# yedek_aviyonik.net
KiCad netlist of a schematic drawn in Altium Designer
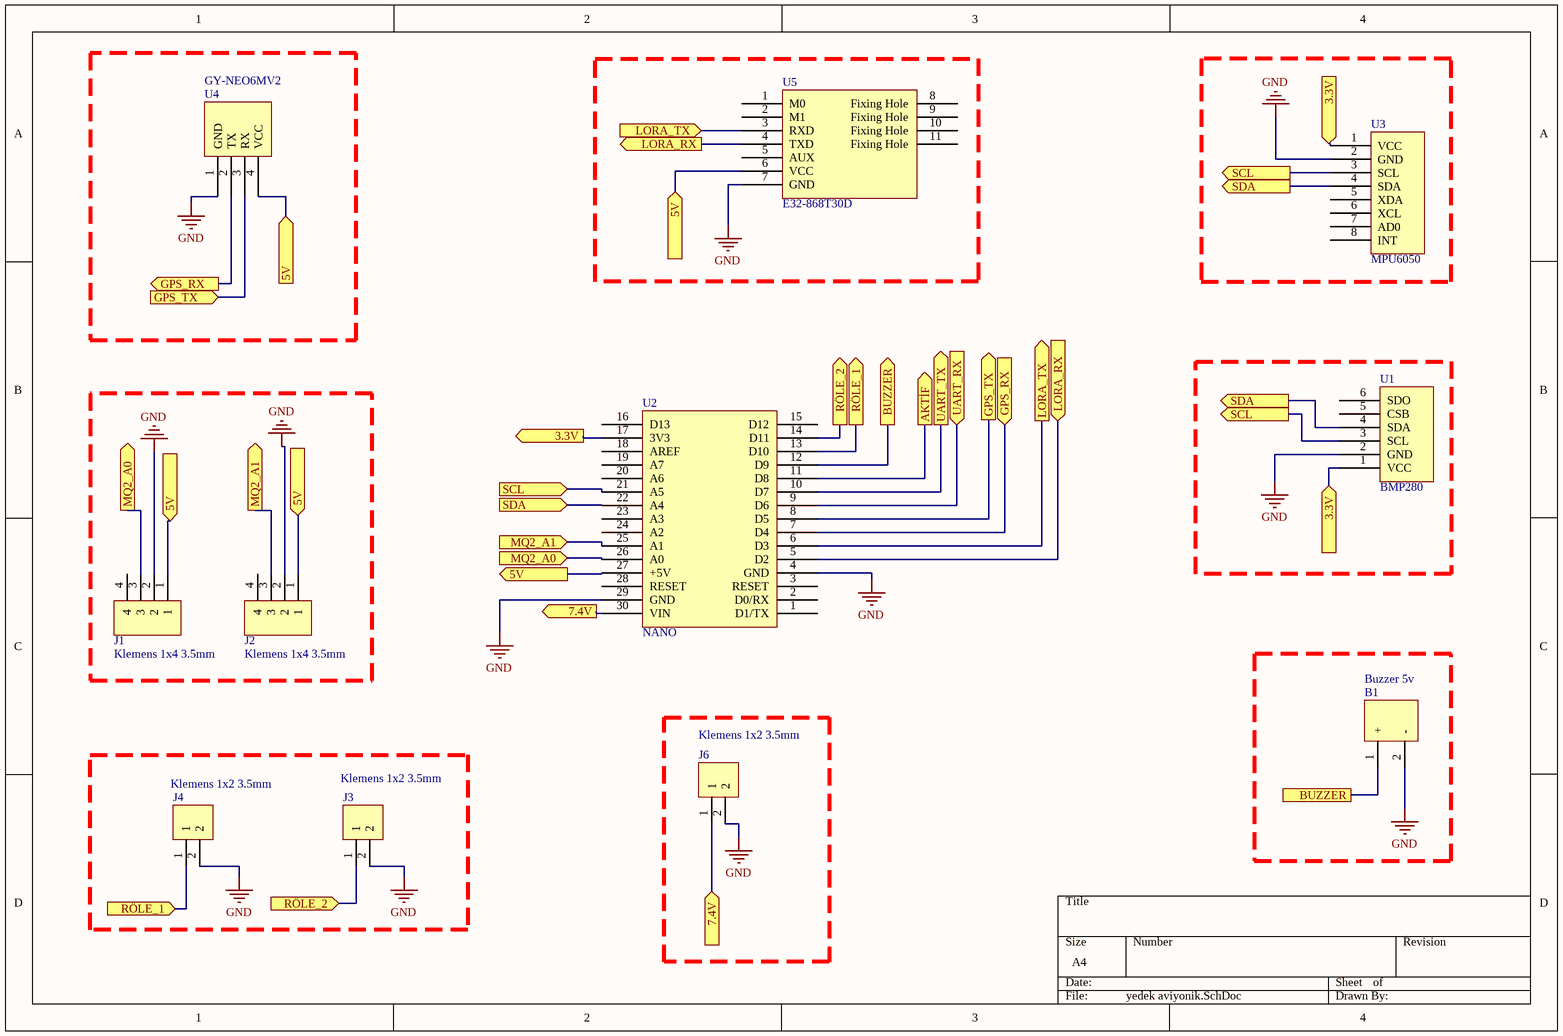
[diagram p0: yedek aviyonik.SchDoc]

(export (version "E")
  (design (tool "Eeschema 10.0.6"))
  (components
    (comp (ref "B1")
      (value "Buzzer 5v")
      (footprint "Buzzer 5v")
      (libsource (lib "deneme") (part "Buzzer 5v"))
    )
    (comp (ref "J1")
      (value "Klemens 1x4 3.5mm")
      (footprint "Klemens 1x4 - 3.5mm")
      (description "Klemens 1x2 3.5mm")
      (libsource (lib "deneme") (part "Klemens 1x4 3.5mm"))
    )
    (comp (ref "J2")
      (value "Klemens 1x4 3.5mm")
      (footprint "Klemens 1x4 - 3.5mm")
      (description "Klemens 1x2 3.5mm")
      (libsource (lib "deneme") (part "Klemens 1x4 3.5mm"))
    )
    (comp (ref "J3")
      (value "Klemens 1x2 3.5mm")
      (footprint "Klemens 1x2 - 3.5mm")
      (libsource (lib "deneme") (part "Klemens 1x2 3.5mm"))
    )
    (comp (ref "J4")
      (value "Klemens 1x2 3.5mm")
      (footprint "Klemens 1x2 - 3.5mm")
      (libsource (lib "deneme") (part "Klemens 1x2 3.5mm"))
    )
    (comp (ref "J6")
      (value "Klemens 1x2 3.5mm")
      (footprint "Klemens 1x2 - 3.5mm")
      (libsource (lib "deneme_yedek") (part "Klemens 1x2 3.5mm"))
    )
    (comp (ref "U1") (value "BMP280") (footprint "BMP280") (libsource (lib "deneme") (part "BMP280")))
    (comp (ref "U2") (value "NANO") (footprint "nano") (libsource (lib "deneme") (part "NANO")))
    (comp (ref "U3") (value "MPU6050") (footprint "MPU6050") (libsource (lib "deneme") (part "MPU6050")))
    (comp (ref "U4")
      (value "GY-NEO6MV2")
      (footprint "GY-NEO6MV2")
      (libsource (lib "deneme") (part "GY-NEO6MV2"))
    )
    (comp (ref "U5")
      (value "E32-868T30D")
      (footprint "E32-868T30D")
      (libsource (lib "deneme") (part "E32-868T30D"))
    )
  )
  (nets
    (net (code "1") (name "/3.3V") (class "Default")
      (node (ref "U1") (pin "1") (pinfunction "VCC_1") (pintype "passive"))
      (node (ref "U2") (pin "17") (pinfunction "3V3_17") (pintype "passive"))
      (node (ref "U3") (pin "1") (pinfunction "VCC_1") (pintype "passive"))
    )
    (net (code "2") (name "/5V") (class "Default")
      (node (ref "J1") (pin "1") (pinfunction "1_1") (pintype "passive"))
      (node (ref "J2") (pin "1") (pinfunction "1_1") (pintype "passive"))
      (node (ref "U2") (pin "27") (pinfunction "+5V_27") (pintype "passive"))
      (node (ref "U4") (pin "4") (pinfunction "VCC_4") (pintype "passive"))
      (node (ref "U5") (pin "6") (pinfunction "VCC_6") (pintype "passive"))
    )
    (net (code "3") (name "/7.4V") (class "Default")
      (node (ref "J6") (pin "1") (pinfunction "1_1") (pintype "passive"))
      (node (ref "U2") (pin "30") (pinfunction "VIN_30") (pintype "passive"))
    )
    (net (code "4") (name "/AKTİF") (class "Default")
      (node (ref "U2") (pin "11") (pinfunction "D8_11") (pintype "passive"))
    )
    (net (code "5") (name "/BUZZER") (class "Default")
      (node (ref "B1") (pin "1") (pinfunction "+_1") (pintype "passive"))
      (node (ref "U2") (pin "12") (pinfunction "D9_12") (pintype "passive"))
    )
    (net (code "6") (name "/GPS_RX") (class "Default")
      (node (ref "U2") (pin "7") (pinfunction "D4_7") (pintype "passive"))
      (node (ref "U4") (pin "2") (pinfunction "TX_2") (pintype "passive"))
    )
    (net (code "7") (name "/GPS_TX") (class "Default")
      (node (ref "U2") (pin "8") (pinfunction "D5_8") (pintype "passive"))
      (node (ref "U4") (pin "3") (pinfunction "RX_3") (pintype "passive"))
    )
    (net (code "8") (name "/LORA_RX") (class "Default")
      (node (ref "U2") (pin "5") (pinfunction "D2_5") (pintype "passive"))
      (node (ref "U5") (pin "4") (pinfunction "TXD_4") (pintype "passive"))
    )
    (net (code "9") (name "/LORA_TX") (class "Default")
      (node (ref "U2") (pin "6") (pinfunction "D3_6") (pintype "passive"))
      (node (ref "U5") (pin "3") (pinfunction "RXD_3") (pintype "passive"))
    )
    (net (code "10") (name "/MQ2_A0") (class "Default")
      (node (ref "J1") (pin "3") (pinfunction "3_3") (pintype "passive"))
      (node (ref "U2") (pin "26") (pinfunction "A0_26") (pintype "passive"))
    )
    (net (code "11") (name "/MQ2_A1") (class "Default")
      (node (ref "J2") (pin "3") (pinfunction "3_3") (pintype "passive"))
      (node (ref "U2") (pin "25") (pinfunction "A1_25") (pintype "passive"))
    )
    (net (code "12") (name "/RÖLE_1") (class "Default")
      (node (ref "J4") (pin "1") (pinfunction "1_1") (pintype "passive"))
      (node (ref "U2") (pin "13") (pinfunction "D10_13") (pintype "passive"))
    )
    (net (code "13") (name "/RÖLE_2") (class "Default")
      (node (ref "J3") (pin "1") (pinfunction "1_1") (pintype "passive"))
      (node (ref "U2") (pin "14") (pinfunction "D11_14") (pintype "passive"))
    )
    (net (code "14") (name "/SCL") (class "Default")
      (node (ref "U1") (pin "3") (pinfunction "SCL_3") (pintype "passive"))
      (node (ref "U2") (pin "21") (pinfunction "A5_21") (pintype "passive"))
      (node (ref "U3") (pin "3") (pinfunction "SCL_3") (pintype "passive"))
    )
    (net (code "15") (name "/SDA") (class "Default")
      (node (ref "U1") (pin "4") (pinfunction "SDA_4") (pintype "passive"))
      (node (ref "U2") (pin "22") (pinfunction "A4_22") (pintype "passive"))
      (node (ref "U3") (pin "4") (pinfunction "SDA_4") (pintype "passive"))
    )
    (net (code "16") (name "/UART_RX") (class "Default")
      (node (ref "U2") (pin "9") (pinfunction "D6_9") (pintype "passive"))
    )
    (net (code "17") (name "/UART_TX") (class "Default")
      (node (ref "U2") (pin "10") (pinfunction "D7_10") (pintype "passive"))
    )
    (net (code "18") (name "GND") (class "Default")
      (node (ref "B1") (pin "2") (pinfunction "-_2") (pintype "passive"))
      (node (ref "J1") (pin "2") (pinfunction "2_2") (pintype "passive"))
      (node (ref "J2") (pin "2") (pinfunction "2_2") (pintype "passive"))
      (node (ref "J3") (pin "2") (pinfunction "2_2") (pintype "passive"))
      (node (ref "J4") (pin "2") (pinfunction "2_2") (pintype "passive"))
      (node (ref "J6") (pin "2") (pinfunction "2_2") (pintype "passive"))
      (node (ref "U1") (pin "2") (pinfunction "GND_2") (pintype "passive"))
      (node (ref "U2") (pin "29") (pinfunction "GND_29") (pintype "passive"))
      (node (ref "U2") (pin "4") (pinfunction "GND_4") (pintype "passive"))
      (node (ref "U3") (pin "2") (pinfunction "GND_2") (pintype "passive"))
      (node (ref "U4") (pin "1") (pinfunction "GND_1") (pintype "passive"))
      (node (ref "U5") (pin "7") (pinfunction "GND_7") (pintype "passive"))
    )
    (net (code "19") (name "unconnected-(J1-Pad4)") (class "Default")
      (node (ref "J1") (pin "4") (pinfunction "4_4") (pintype "passive"))
    )
    (net (code "20") (name "unconnected-(J2-Pad4)") (class "Default")
      (node (ref "J2") (pin "4") (pinfunction "4_4") (pintype "passive"))
    )
    (net (code "21") (name "unconnected-(U1-CSB-Pad5)") (class "Default")
      (node (ref "U1") (pin "5") (pinfunction "CSB_5") (pintype "passive"))
    )
    (net (code "22") (name "unconnected-(U1-SDO-Pad6)") (class "Default")
      (node (ref "U1") (pin "6") (pinfunction "SDO_6") (pintype "passive"))
    )
    (net (code "23") (name "unconnected-(U2-A2-Pad24)") (class "Default")
      (node (ref "U2") (pin "24") (pinfunction "A2_24") (pintype "passive"))
    )
    (net (code "24") (name "unconnected-(U2-A3-Pad23)") (class "Default")
      (node (ref "U2") (pin "23") (pinfunction "A3_23") (pintype "passive"))
    )
    (net (code "25") (name "unconnected-(U2-A6-Pad20)") (class "Default")
      (node (ref "U2") (pin "20") (pinfunction "A6_20") (pintype "passive"))
    )
    (net (code "26") (name "unconnected-(U2-A7-Pad19)") (class "Default")
      (node (ref "U2") (pin "19") (pinfunction "A7_19") (pintype "passive"))
    )
    (net (code "27") (name "unconnected-(U2-AREF-Pad18)") (class "Default")
      (node (ref "U2") (pin "18") (pinfunction "AREF_18") (pintype "passive"))
    )
    (net (code "28") (name "unconnected-(U2-D0{slash}RX-Pad2)") (class "Default")
      (node (ref "U2") (pin "2") (pinfunction "D0/RX_2") (pintype "passive"))
    )
    (net (code "29") (name "unconnected-(U2-D1{slash}TX-Pad1)") (class "Default")
      (node (ref "U2") (pin "1") (pinfunction "D1/TX_1") (pintype "passive"))
    )
    (net (code "30") (name "unconnected-(U2-D12-Pad15)") (class "Default")
      (node (ref "U2") (pin "15") (pinfunction "D12_15") (pintype "passive"))
    )
    (net (code "31") (name "unconnected-(U2-D13-Pad16)") (class "Default")
      (node (ref "U2") (pin "16") (pinfunction "D13_16") (pintype "passive"))
    )
    (net (code "32") (name "unconnected-(U2-RESET-Pad3)") (class "Default")
      (node (ref "U2") (pin "3") (pinfunction "RESET_3") (pintype "passive"))
    )
    (net (code "33") (name "unconnected-(U2-RESET-Pad28)") (class "Default")
      (node (ref "U2") (pin "28") (pinfunction "RESET_28") (pintype "passive"))
    )
    (net (code "34") (name "unconnected-(U3-AD0-Pad7)") (class "Default")
      (node (ref "U3") (pin "7") (pinfunction "AD0_7") (pintype "passive"))
    )
    (net (code "35") (name "unconnected-(U3-INT-Pad8)") (class "Default")
      (node (ref "U3") (pin "8") (pinfunction "INT_8") (pintype "passive"))
    )
    (net (code "36") (name "unconnected-(U3-XCL-Pad6)") (class "Default")
      (node (ref "U3") (pin "6") (pinfunction "XCL_6") (pintype "passive"))
    )
    (net (code "37") (name "unconnected-(U3-XDA-Pad5)") (class "Default")
      (node (ref "U3") (pin "5") (pinfunction "XDA_5") (pintype "passive"))
    )
    (net (code "38") (name "unconnected-(U5-AUX-Pad5)") (class "Default")
      (node (ref "U5") (pin "5") (pinfunction "AUX_5") (pintype "passive"))
    )
    (net (code "39") (name "unconnected-(U5-Fixing_Hole-Pad8)") (class "Default")
      (node (ref "U5") (pin "8") (pinfunction "Fixing_Hole_8") (pintype "passive"))
    )
    (net (code "40") (name "unconnected-(U5-Fixing_Hole-Pad9)") (class "Default")
      (node (ref "U5") (pin "9") (pinfunction "Fixing_Hole_9") (pintype "passive"))
    )
    (net (code "41") (name "unconnected-(U5-Fixing_Hole-Pad10)") (class "Default")
      (node (ref "U5") (pin "10") (pinfunction "Fixing_Hole_10") (pintype "passive"))
    )
    (net (code "42") (name "unconnected-(U5-Fixing_Hole-Pad11)") (class "Default")
      (node (ref "U5") (pin "11") (pinfunction "Fixing_Hole_11") (pintype "passive"))
    )
    (net (code "43") (name "unconnected-(U5-M0-Pad1)") (class "Default")
      (node (ref "U5") (pin "1") (pinfunction "M0_1") (pintype "passive"))
    )
    (net (code "44") (name "unconnected-(U5-M1-Pad2)") (class "Default")
      (node (ref "U5") (pin "2") (pinfunction "M1_2") (pintype "passive"))
    )
  )
)
